# FlightComputer_DeploymentBoard_Rev_B.net
KiCad netlist of a schematic drawn in EAGLE
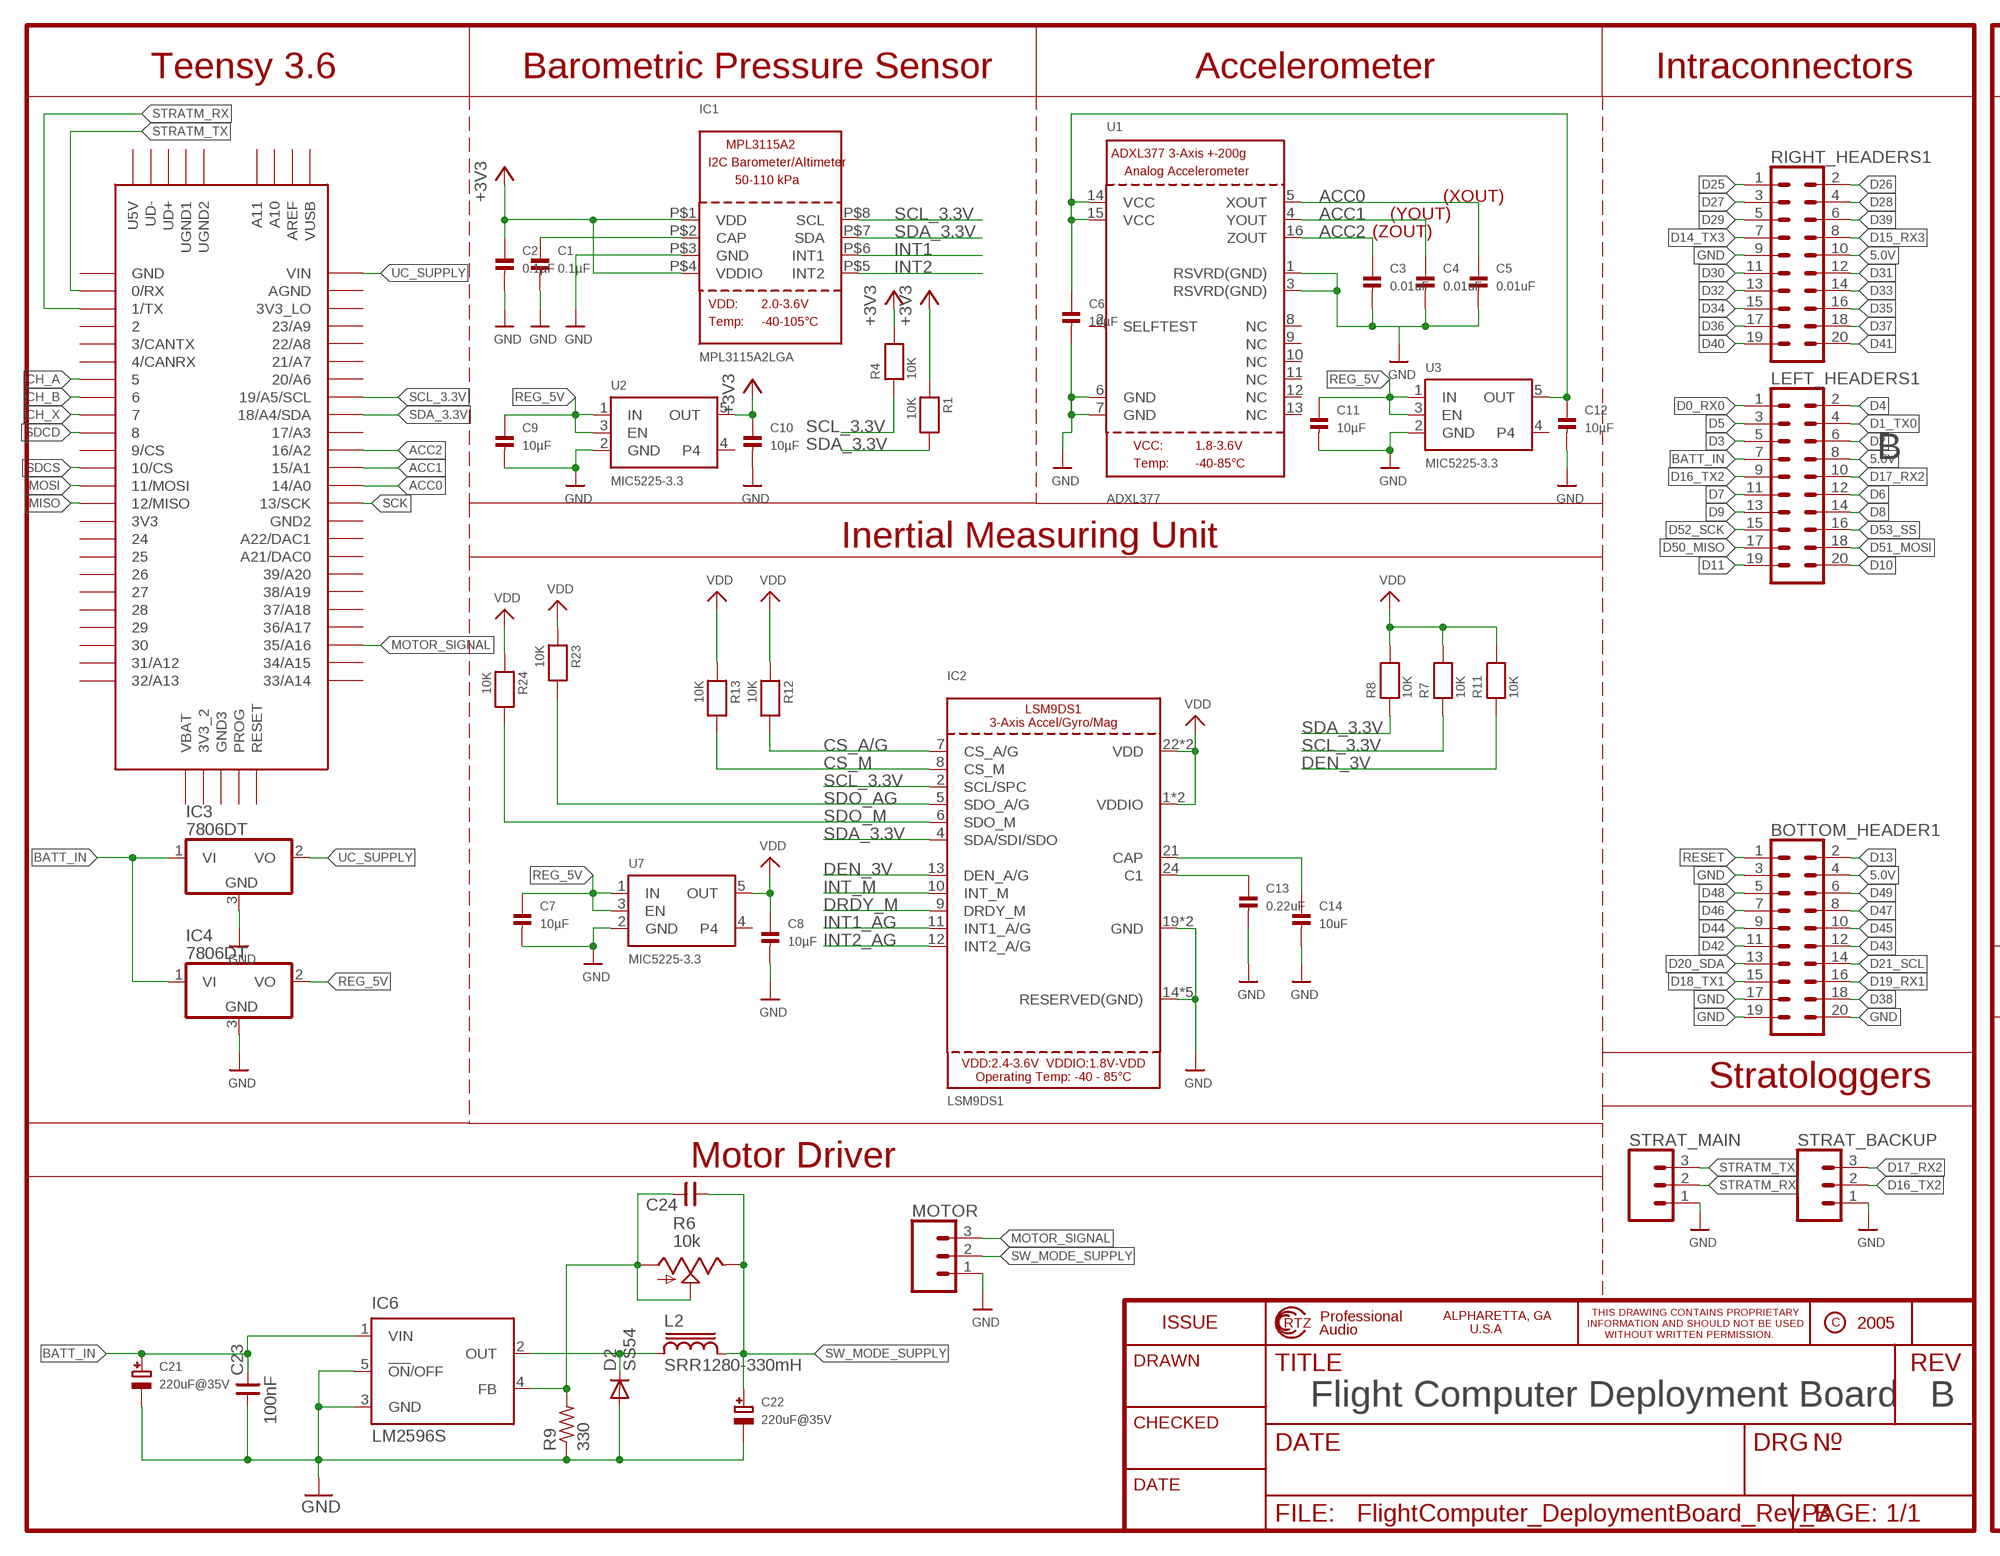
[diagram p0: schematic, sheet 1, part 1 of 2]
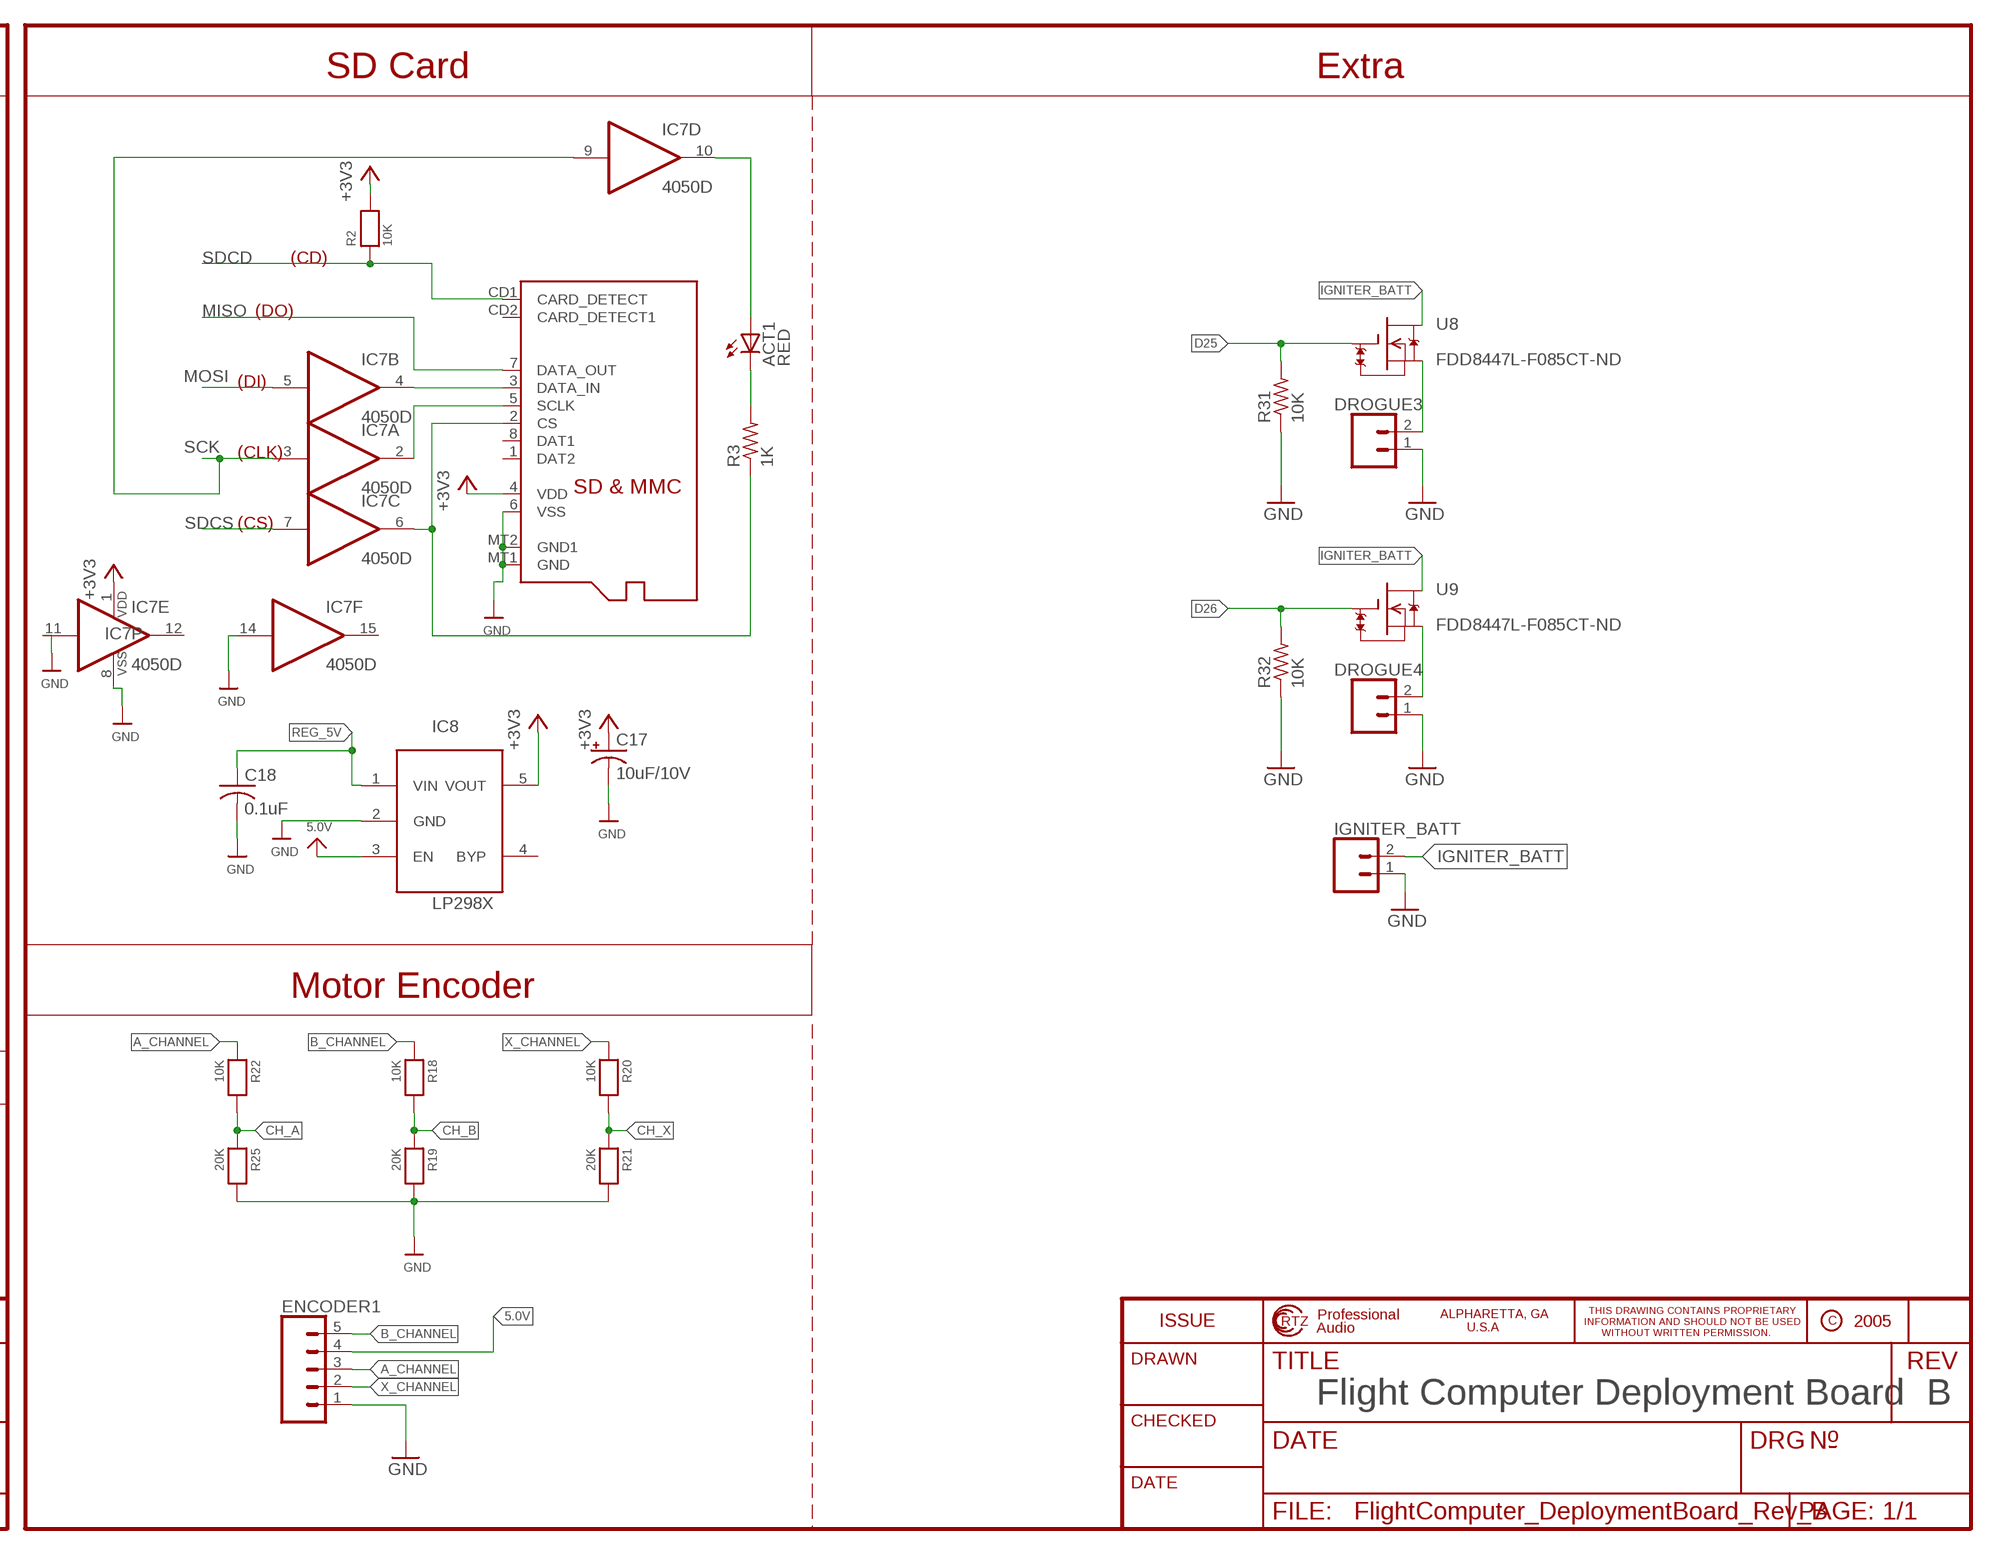
[diagram p1: schematic, sheet 1, part 2 of 2]

(export (version "E")
  (design (tool "Eeschema 10.0.6"))
  (components
    (comp (ref "ACT1")
      (value "RED")
      (footprint "eagle-import:CHIP-LED0805")
      (libsource (lib "eagle-import") (part "LEDCHIP-LED0805"))
    )
    (comp (ref "BOTTOM_HEADER1")
      (value "CONN_10X2")
      (footprint "eagle-import:2X10")
      (libsource (lib "eagle-import") (part "CONN_10X2"))
    )
    (comp (ref "C1")
      (value "0.1µF")
      (footprint "eagle-import:0603")
      (libsource (lib "eagle-import") (part "CAP_CERAMIC0603"))
    )
    (comp (ref "C2")
      (value "0.1µF")
      (footprint "eagle-import:0603")
      (libsource (lib "eagle-import") (part "CAP_CERAMIC0603"))
    )
    (comp (ref "C3")
      (value "0.01uF")
      (footprint "eagle-import:0603")
      (libsource (lib "eagle-import") (part "CAP_CERAMIC0603"))
    )
    (comp (ref "C4")
      (value "0.01uF")
      (footprint "eagle-import:0603")
      (libsource (lib "eagle-import") (part "CAP_CERAMIC0603"))
    )
    (comp (ref "C5")
      (value "0.01uF")
      (footprint "eagle-import:0603")
      (libsource (lib "eagle-import") (part "CAP_CERAMIC0603"))
    )
    (comp (ref "C6")
      (value "10µF")
      (footprint "eagle-import:0603")
      (libsource (lib "eagle-import") (part "CAP_CERAMIC0603"))
    )
    (comp (ref "C7")
      (value "10µF")
      (footprint "eagle-import:0603")
      (libsource (lib "eagle-import") (part "CAP_CERAMIC0603"))
    )
    (comp (ref "C8")
      (value "10µF")
      (footprint "eagle-import:0603")
      (libsource (lib "eagle-import") (part "CAP_CERAMIC0603"))
    )
    (comp (ref "C9")
      (value "10µF")
      (footprint "eagle-import:0603")
      (libsource (lib "eagle-import") (part "CAP_CERAMIC0603"))
    )
    (comp (ref "C10")
      (value "10µF")
      (footprint "eagle-import:0603")
      (libsource (lib "eagle-import") (part "CAP_CERAMIC0603"))
    )
    (comp (ref "C11")
      (value "10µF")
      (footprint "eagle-import:0603")
      (libsource (lib "eagle-import") (part "CAP_CERAMIC0603"))
    )
    (comp (ref "C12")
      (value "10µF")
      (footprint "eagle-import:0603")
      (libsource (lib "eagle-import") (part "CAP_CERAMIC0603"))
    )
    (comp (ref "C13")
      (value "0.22uF")
      (footprint "eagle-import:0603")
      (libsource (lib "eagle-import") (part "CAP_CERAMIC0603"))
    )
    (comp (ref "C14")
      (value "10uF")
      (footprint "eagle-import:0603")
      (libsource (lib "eagle-import") (part "CAP_CERAMIC0603"))
    )
    (comp (ref "C17")
      (value "10uF/10V")
      (footprint "eagle-import:A_3216-18R")
      (libsource (lib "eagle-import") (part "CPOL-USA/3216-18R"))
    )
    (comp (ref "C18")
      (value "0.1uF")
      (footprint "eagle-import:C0805K")
      (libsource (lib "eagle-import") (part "C-USC0805K"))
    )
    (comp (ref "C21")
      (value "220uF@35V")
      (footprint "eagle-import:PANASONIC_D")
      (libsource (lib "eagle-import") (part "CAP_ELECTROLYTICPANASONIC_D"))
    )
    (comp (ref "C22")
      (value "220uF@35V")
      (footprint "eagle-import:PANASONIC_D")
      (libsource (lib "eagle-import") (part "CAP_ELECTROLYTICPANASONIC_D"))
    )
    (comp (ref "C23")
      (value "100nF")
      (footprint "eagle-import:0603")
      (libsource (lib "eagle-import") (part "CNP-0603"))
    )
    (comp (ref "C24")
      (value "CNP-0603")
      (footprint "eagle-import:0603")
      (libsource (lib "eagle-import") (part "CNP-0603"))
    )
    (comp (ref "D2")
      (value "SS54")
      (footprint "eagle-import:DO214AB")
      (fields (field (name "MF") "Fairchild") (field (name "MPN") "S3G"))
      (libsource (lib "eagle-import") (part "S3G"))
    )
    (comp (ref "DROGUE3")
      (value "CONN_023.5MM")
      (footprint "eagle-import:SCREWTERMINAL-3.5MM-2")
      (libsource (lib "eagle-import") (part "CONN_023.5MM"))
    )
    (comp (ref "DROGUE4")
      (value "CONN_023.5MM")
      (footprint "eagle-import:SCREWTERMINAL-3.5MM-2")
      (libsource (lib "eagle-import") (part "CONN_023.5MM"))
    )
    (comp (ref "ENCODER1")
      (value "CONN_05")
      (footprint "eagle-import:1X05")
      (libsource (lib "eagle-import") (part "CONN_05"))
    )
    (comp (ref "IC1")
      (value "MPL3115A2LGA")
      (footprint "eagle-import:LGA8")
      (libsource (lib "eagle-import") (part "MPL3115A2LGA"))
    )
    (comp (ref "IC2")
      (value "LSM9DS1")
      (footprint "eagle-import:LGA24_3.5X3.1MM")
      (libsource (lib "eagle-import") (part "LSM9DS1"))
    )
    (comp (ref "IC3")
      (value "7806DT")
      (footprint "eagle-import:TO252")
      (libsource (lib "eagle-import") (part "78DT06"))
    )
    (comp (ref "IC4")
      (value "7806DT")
      (footprint "eagle-import:TO252")
      (libsource (lib "eagle-import") (part "78DT06"))
    )
    (comp (ref "IC6")
      (value "LM2596S")
      (footprint "eagle-import:TO263-5")
      (fields (field (name "MF") "NATIONAL SEMICONDUCTOR") (field (name "MPN") "LM2596S-ADJ/NOPB"))
      (libsource (lib "eagle-import") (part "LM2596S"))
    )
    (comp (ref "IC7")
      (value "4050D")
      (footprint "eagle-import:SO16")
      (libsource (lib "eagle-import") (part "4050D"))
    )
    (comp (ref "IC8")
      (value "LP298XS")
      (footprint "eagle-import:SOT23-5L")
      (libsource (lib "eagle-import") (part "LP298XS"))
    )
    (comp (ref "IGNITER_BATT")
      (value "CONN_02")
      (footprint "eagle-import:1X02")
      (libsource (lib "eagle-import") (part "CONN_02"))
    )
    (comp (ref "L2")
      (value "SRR1280-330mH")
      (footprint "eagle-import:SRR1280")
      (libsource (lib "eagle-import") (part "SRR1280"))
    )
    (comp (ref "LEFT_HEADERS1")
      (value "CONN_10X2")
      (footprint "eagle-import:2X10")
      (libsource (lib "eagle-import") (part "CONN_10X2"))
    )
    (comp (ref "MOTOR")
      (value "CONN_03")
      (footprint "eagle-import:1X03")
      (libsource (lib "eagle-import") (part "CONN_03"))
    )
    (comp (ref "R1")
      (value "10K")
      (footprint "eagle-import:0603")
      (libsource (lib "eagle-import") (part "RESISTOR0603"))
    )
    (comp (ref "R2")
      (value "10K")
      (footprint "eagle-import:0603")
      (libsource (lib "eagle-import") (part "RESISTOR0603"))
    )
    (comp (ref "R3")
      (value "1K")
      (footprint "eagle-import:R0805")
      (libsource (lib "eagle-import") (part "R-US_R0805"))
    )
    (comp (ref "R4")
      (value "10K")
      (footprint "eagle-import:0603")
      (libsource (lib "eagle-import") (part "RESISTOR0603"))
    )
    (comp (ref "R6")
      (value "10k")
      (footprint "eagle-import:S64W")
      (libsource (lib "eagle-import") (part "TRIM_US-S64W"))
    )
    (comp (ref "R7")
      (value "10K")
      (footprint "eagle-import:0603")
      (libsource (lib "eagle-import") (part "RESISTOR0603"))
    )
    (comp (ref "R8")
      (value "10K")
      (footprint "eagle-import:0603")
      (libsource (lib "eagle-import") (part "RESISTOR0603"))
    )
    (comp (ref "R9")
      (value "330")
      (footprint "eagle-import:R0603")
      (libsource (lib "eagle-import") (part "R-US_R0603"))
    )
    (comp (ref "R11")
      (value "10K")
      (footprint "eagle-import:0603")
      (libsource (lib "eagle-import") (part "RESISTOR0603"))
    )
    (comp (ref "R12")
      (value "10K")
      (footprint "eagle-import:0603")
      (libsource (lib "eagle-import") (part "RESISTOR0603"))
    )
    (comp (ref "R13")
      (value "10K")
      (footprint "eagle-import:0603")
      (libsource (lib "eagle-import") (part "RESISTOR0603"))
    )
    (comp (ref "R18")
      (value "10K")
      (footprint "eagle-import:0603")
      (libsource (lib "eagle-import") (part "RESISTOR0603"))
    )
    (comp (ref "R19")
      (value "20K")
      (footprint "eagle-import:0603")
      (libsource (lib "eagle-import") (part "RESISTOR0603"))
    )
    (comp (ref "R20")
      (value "10K")
      (footprint "eagle-import:0603")
      (libsource (lib "eagle-import") (part "RESISTOR0603"))
    )
    (comp (ref "R21")
      (value "20K")
      (footprint "eagle-import:0603")
      (libsource (lib "eagle-import") (part "RESISTOR0603"))
    )
    (comp (ref "R22")
      (value "10K")
      (footprint "eagle-import:0603")
      (libsource (lib "eagle-import") (part "RESISTOR0603"))
    )
    (comp (ref "R23")
      (value "10K")
      (footprint "eagle-import:0603")
      (libsource (lib "eagle-import") (part "RESISTOR0603"))
    )
    (comp (ref "R24")
      (value "10K")
      (footprint "eagle-import:0603")
      (libsource (lib "eagle-import") (part "RESISTOR0603"))
    )
    (comp (ref "R25")
      (value "20K")
      (footprint "eagle-import:0603")
      (libsource (lib "eagle-import") (part "RESISTOR0603"))
    )
    (comp (ref "R31")
      (value "10K")
      (footprint "eagle-import:R0805")
      (libsource (lib "eagle-import") (part "R-US_R0805"))
    )
    (comp (ref "R32")
      (value "10K")
      (footprint "eagle-import:R0805")
      (libsource (lib "eagle-import") (part "R-US_R0805"))
    )
    (comp (ref "RIGHT_HEADERS1")
      (value "CONN_10X2")
      (footprint "eagle-import:2X10")
      (libsource (lib "eagle-import") (part "CONN_10X2"))
    )
    (comp (ref "STRAT_BACKUP")
      (value "CONN_03")
      (footprint "eagle-import:1X03")
      (libsource (lib "eagle-import") (part "SparkFun-Connectors_513_CONN_03"))
    )
    (comp (ref "STRAT_MAIN")
      (value "CONN_03")
      (footprint "eagle-import:1X03")
      (libsource (lib "eagle-import") (part "SparkFun-Connectors_513_CONN_03"))
    )
    (comp (ref "U$1")
      (value "TEENSY_3.5/3.6")
      (footprint "eagle-import:TEENSY_3.5_3.6")
      (libsource (lib "eagle-import") (part "TEENSY_3.5/3.6"))
    )
    (comp (ref "U$38")
      (value "STRATOLOGGER")
      (footprint "eagle-import:STRATOLOGGER")
      (libsource (lib "eagle-import") (part "STRATOLOGGER"))
    )
    (comp (ref "U1")
      (value "ADXL377")
      (footprint "eagle-import:LFCSP16_LQ")
      (libsource (lib "eagle-import") (part "ACCEL_ADXL377"))
    )
    (comp (ref "U2")
      (value "MIC5225-3.3")
      (footprint "eagle-import:SOT23-5")
      (libsource (lib "eagle-import") (part "VREG_SOT23-5"))
    )
    (comp (ref "U3")
      (value "MIC5225-3.3")
      (footprint "eagle-import:SOT23-5")
      (libsource (lib "eagle-import") (part "VREG_SOT23-5"))
    )
    (comp (ref "U7")
      (value "MIC5225-3.3")
      (footprint "eagle-import:SOT23-5")
      (libsource (lib "eagle-import") (part "VREG_SOT23-5"))
    )
    (comp (ref "U8")
      (value "FDD8447L-F085CT-ND")
      (footprint "eagle-import:TO252")
      (libsource (lib "eagle-import") (part "TSM4ND50"))
    )
    (comp (ref "U9")
      (value "FDD8447L-F085CT-ND")
      (footprint "eagle-import:TO252")
      (libsource (lib "eagle-import") (part "TSM4ND50"))
    )
    (comp (ref "X2")
      (value "MICROSD")
      (footprint "eagle-import:MICROSD")
      (libsource (lib "eagle-import") (part "MICROSD"))
    )
  )
  (nets
    (net (code "1") (name "+3V3") (class "Default")
      (node (ref "C10") (pin "1") (pinfunction "P$1_1") (pintype "passive"))
      (node (ref "C17") (pin "+") (pinfunction "+_+") (pintype "passive"))
      (node (ref "C2") (pin "1") (pinfunction "P$1_1") (pintype "passive"))
      (node (ref "IC1") (pin "P$1") (pinfunction "VDD_P$1") (pintype "power_in"))
      (node (ref "IC1") (pin "P$4") (pinfunction "VDDIO_P$4") (pintype "power_in"))
      (node (ref "IC7") (pin "1") (pinfunction "VDD_1") (pintype "power_in"))
      (node (ref "IC8") (pin "5") (pinfunction "VOUT_5") (pintype "bidirectional"))
      (node (ref "R1") (pin "1") (pinfunction "1_1") (pintype "passive"))
      (node (ref "R2") (pin "2") (pinfunction "2_2") (pintype "passive"))
      (node (ref "R4") (pin "2") (pinfunction "2_2") (pintype "passive"))
      (node (ref "U2") (pin "5") (pinfunction "OUT_5") (pintype "power_in"))
      (node (ref "X2") (pin "4") (pinfunction "VDD_4") (pintype "power_in"))
    )
    (net (code "2") (name "/CS_A{slash}G") (class "Default")
      (node (ref "IC2") (pin "7") (pinfunction "CS_A/G_7") (pintype "bidirectional"))
      (node (ref "R12") (pin "2") (pinfunction "2_2") (pintype "passive"))
    )
    (net (code "3") (name "/CS_M") (class "Default")
      (node (ref "IC2") (pin "8") (pinfunction "CS_M_8") (pintype "bidirectional"))
      (node (ref "R13") (pin "2") (pinfunction "2_2") (pintype "passive"))
    )
    (net (code "4") (name "/DEN_3V") (class "Default")
      (node (ref "IC2") (pin "13") (pinfunction "DEN_A/G_13") (pintype "bidirectional"))
      (node (ref "R11") (pin "1") (pinfunction "1_1") (pintype "passive"))
    )
    (net (code "5") (name "/DRDY_M") (class "Default")
      (node (ref "IC2") (pin "9") (pinfunction "DRDY_M_9") (pintype "bidirectional"))
    )
    (net (code "6") (name "/INT1") (class "Default")
      (node (ref "IC1") (pin "P$6") (pinfunction "INT1_P$6") (pintype "output"))
    )
    (net (code "7") (name "/INT1_AG") (class "Default")
      (node (ref "IC2") (pin "11") (pinfunction "INT1_A/G_11") (pintype "bidirectional"))
    )
    (net (code "8") (name "/INT2") (class "Default")
      (node (ref "IC1") (pin "P$5") (pinfunction "INT2_P$5") (pintype "output"))
    )
    (net (code "9") (name "/INT2_AG") (class "Default")
      (node (ref "IC2") (pin "12") (pinfunction "INT2_A/G_12") (pintype "bidirectional"))
    )
    (net (code "10") (name "/INT_M") (class "Default")
      (node (ref "IC2") (pin "10") (pinfunction "INT_M_10") (pintype "bidirectional"))
    )
    (net (code "11") (name "/SDO_AG") (class "Default")
      (node (ref "IC2") (pin "5") (pinfunction "SDO_A/G_5") (pintype "bidirectional"))
      (node (ref "R23") (pin "2") (pinfunction "2_2") (pintype "passive"))
    )
    (net (code "12") (name "/SDO_M") (class "Default")
      (node (ref "IC2") (pin "6") (pinfunction "SDO_M_6") (pintype "bidirectional"))
      (node (ref "R24") (pin "2") (pinfunction "2_2") (pintype "passive"))
    )
    (net (code "13") (name "5.0V") (class "Default")
      (node (ref "BOTTOM_HEADER1") (pin "4") (pinfunction "4_4") (pintype "passive"))
      (node (ref "ENCODER1") (pin "4") (pinfunction "4_4") (pintype "passive"))
      (node (ref "IC8") (pin "3") (pinfunction "EN_3") (pintype "bidirectional"))
      (node (ref "LEFT_HEADERS1") (pin "8") (pinfunction "8_8") (pintype "passive"))
      (node (ref "RIGHT_HEADERS1") (pin "10") (pinfunction "10_10") (pintype "passive"))
    )
    (net (code "14") (name "ACC0") (class "Default")
      (node (ref "C5") (pin "1") (pinfunction "P$1_1") (pintype "passive"))
      (node (ref "U$1") (pin "14/A0") (pinfunction "14/A0_14/A0") (pintype "bidirectional"))
      (node (ref "U1") (pin "5") (pinfunction "XOUT_5") (pintype "output"))
    )
    (net (code "15") (name "ACC1") (class "Default")
      (node (ref "C4") (pin "1") (pinfunction "P$1_1") (pintype "passive"))
      (node (ref "U$1") (pin "15/A1") (pinfunction "15/A1_15/A1") (pintype "bidirectional"))
      (node (ref "U1") (pin "4") (pinfunction "YOUT_4") (pintype "output"))
    )
    (net (code "16") (name "ACC2") (class "Default")
      (node (ref "C3") (pin "1") (pinfunction "P$1_1") (pintype "passive"))
      (node (ref "U$1") (pin "16/A2") (pinfunction "16/A2_16/A2") (pintype "bidirectional"))
      (node (ref "U1") (pin "16") (pinfunction "ZOUT_16") (pintype "output"))
    )
    (net (code "17") (name "A_CHANNEL") (class "Default")
      (node (ref "ENCODER1") (pin "3") (pinfunction "3_3") (pintype "passive"))
      (node (ref "R22") (pin "1") (pinfunction "1_1") (pintype "passive"))
    )
    (net (code "18") (name "BATT_IN") (class "Default")
      (node (ref "C21") (pin "+") (pinfunction "+_+") (pintype "passive"))
      (node (ref "C23") (pin "2") (pinfunction "2_2") (pintype "passive"))
      (node (ref "IC3") (pin "1") (pinfunction "VI_1") (pintype "input"))
      (node (ref "IC4") (pin "1") (pinfunction "VI_1") (pintype "input"))
      (node (ref "IC6") (pin "1") (pinfunction "VIN_1") (pintype "input"))
      (node (ref "LEFT_HEADERS1") (pin "7") (pinfunction "7_7") (pintype "passive"))
    )
    (net (code "19") (name "B_CHANNEL") (class "Default")
      (node (ref "ENCODER1") (pin "5") (pinfunction "5_5") (pintype "passive"))
      (node (ref "R18") (pin "1") (pinfunction "1_1") (pintype "passive"))
    )
    (net (code "20") (name "CH_A") (class "Default")
      (node (ref "R22") (pin "2") (pinfunction "2_2") (pintype "passive"))
      (node (ref "R25") (pin "1") (pinfunction "1_1") (pintype "passive"))
      (node (ref "U$1") (pin "5") (pinfunction "5_5") (pintype "bidirectional"))
    )
    (net (code "21") (name "CH_B") (class "Default")
      (node (ref "R18") (pin "2") (pinfunction "2_2") (pintype "passive"))
      (node (ref "R19") (pin "1") (pinfunction "1_1") (pintype "passive"))
      (node (ref "U$1") (pin "6") (pinfunction "6_6") (pintype "bidirectional"))
    )
    (net (code "22") (name "CH_X") (class "Default")
      (node (ref "R20") (pin "2") (pinfunction "2_2") (pintype "passive"))
      (node (ref "R21") (pin "1") (pinfunction "1_1") (pintype "passive"))
      (node (ref "U$1") (pin "7") (pinfunction "7_7") (pintype "bidirectional"))
    )
    (net (code "23") (name "D0_RX0") (class "Default")
      (node (ref "LEFT_HEADERS1") (pin "1") (pinfunction "1_1") (pintype "passive"))
    )
    (net (code "24") (name "D1_TX0") (class "Default")
      (node (ref "LEFT_HEADERS1") (pin "4") (pinfunction "4_4") (pintype "passive"))
    )
    (net (code "25") (name "D2") (class "Default")
      (node (ref "LEFT_HEADERS1") (pin "6") (pinfunction "6_6") (pintype "passive"))
    )
    (net (code "26") (name "D3") (class "Default")
      (node (ref "LEFT_HEADERS1") (pin "5") (pinfunction "5_5") (pintype "passive"))
    )
    (net (code "27") (name "D4") (class "Default")
      (node (ref "LEFT_HEADERS1") (pin "2") (pinfunction "2_2") (pintype "passive"))
    )
    (net (code "28") (name "D5") (class "Default")
      (node (ref "LEFT_HEADERS1") (pin "3") (pinfunction "3_3") (pintype "passive"))
    )
    (net (code "29") (name "D6") (class "Default")
      (node (ref "LEFT_HEADERS1") (pin "12") (pinfunction "12_12") (pintype "passive"))
    )
    (net (code "30") (name "D7") (class "Default")
      (node (ref "LEFT_HEADERS1") (pin "11") (pinfunction "11_11") (pintype "passive"))
    )
    (net (code "31") (name "D8") (class "Default")
      (node (ref "LEFT_HEADERS1") (pin "14") (pinfunction "14_14") (pintype "passive"))
    )
    (net (code "32") (name "D9") (class "Default")
      (node (ref "LEFT_HEADERS1") (pin "13") (pinfunction "13_13") (pintype "passive"))
    )
    (net (code "33") (name "D10") (class "Default")
      (node (ref "LEFT_HEADERS1") (pin "20") (pinfunction "20_20") (pintype "passive"))
    )
    (net (code "34") (name "D11") (class "Default")
      (node (ref "LEFT_HEADERS1") (pin "19") (pinfunction "19_19") (pintype "passive"))
    )
    (net (code "35") (name "D13") (class "Default")
      (node (ref "BOTTOM_HEADER1") (pin "2") (pinfunction "2_2") (pintype "passive"))
    )
    (net (code "36") (name "D14_TX3") (class "Default")
      (node (ref "RIGHT_HEADERS1") (pin "7") (pinfunction "7_7") (pintype "passive"))
    )
    (net (code "37") (name "D15_RX3") (class "Default")
      (node (ref "RIGHT_HEADERS1") (pin "8") (pinfunction "8_8") (pintype "passive"))
    )
    (net (code "38") (name "D16_TX2") (class "Default")
      (node (ref "LEFT_HEADERS1") (pin "9") (pinfunction "9_9") (pintype "passive"))
      (node (ref "STRAT_BACKUP") (pin "2") (pinfunction "2_2") (pintype "passive"))
    )
    (net (code "39") (name "D17_RX2") (class "Default")
      (node (ref "LEFT_HEADERS1") (pin "10") (pinfunction "10_10") (pintype "passive"))
      (node (ref "STRAT_BACKUP") (pin "3") (pinfunction "3_3") (pintype "passive"))
    )
    (net (code "40") (name "D18_TX1") (class "Default")
      (node (ref "BOTTOM_HEADER1") (pin "15") (pinfunction "15_15") (pintype "passive"))
    )
    (net (code "41") (name "D19_RX1") (class "Default")
      (node (ref "BOTTOM_HEADER1") (pin "16") (pinfunction "16_16") (pintype "passive"))
    )
    (net (code "42") (name "D20_SDA") (class "Default")
      (node (ref "BOTTOM_HEADER1") (pin "13") (pinfunction "13_13") (pintype "passive"))
    )
    (net (code "43") (name "D21_SCL") (class "Default")
      (node (ref "BOTTOM_HEADER1") (pin "14") (pinfunction "14_14") (pintype "passive"))
    )
    (net (code "44") (name "D25") (class "Default")
      (node (ref "R31") (pin "2") (pinfunction "2_2") (pintype "passive"))
      (node (ref "RIGHT_HEADERS1") (pin "1") (pinfunction "1_1") (pintype "passive"))
      (node (ref "U8") (pin "G") (pinfunction "G_G") (pintype "passive"))
    )
    (net (code "45") (name "D26") (class "Default")
      (node (ref "R32") (pin "2") (pinfunction "2_2") (pintype "passive"))
      (node (ref "RIGHT_HEADERS1") (pin "2") (pinfunction "2_2") (pintype "passive"))
      (node (ref "U9") (pin "G") (pinfunction "G_G") (pintype "passive"))
    )
    (net (code "46") (name "D27") (class "Default")
      (node (ref "RIGHT_HEADERS1") (pin "3") (pinfunction "3_3") (pintype "passive"))
    )
    (net (code "47") (name "D28") (class "Default")
      (node (ref "RIGHT_HEADERS1") (pin "4") (pinfunction "4_4") (pintype "passive"))
    )
    (net (code "48") (name "D29") (class "Default")
      (node (ref "RIGHT_HEADERS1") (pin "5") (pinfunction "5_5") (pintype "passive"))
    )
    (net (code "49") (name "D30") (class "Default")
      (node (ref "RIGHT_HEADERS1") (pin "11") (pinfunction "11_11") (pintype "passive"))
    )
    (net (code "50") (name "D31") (class "Default")
      (node (ref "RIGHT_HEADERS1") (pin "12") (pinfunction "12_12") (pintype "passive"))
    )
    (net (code "51") (name "D32") (class "Default")
      (node (ref "RIGHT_HEADERS1") (pin "13") (pinfunction "13_13") (pintype "passive"))
    )
    (net (code "52") (name "D33") (class "Default")
      (node (ref "RIGHT_HEADERS1") (pin "14") (pinfunction "14_14") (pintype "passive"))
    )
    (net (code "53") (name "D34") (class "Default")
      (node (ref "RIGHT_HEADERS1") (pin "15") (pinfunction "15_15") (pintype "passive"))
    )
    (net (code "54") (name "D35") (class "Default")
      (node (ref "RIGHT_HEADERS1") (pin "16") (pinfunction "16_16") (pintype "passive"))
    )
    (net (code "55") (name "D36") (class "Default")
      (node (ref "RIGHT_HEADERS1") (pin "17") (pinfunction "17_17") (pintype "passive"))
    )
    (net (code "56") (name "D37") (class "Default")
      (node (ref "RIGHT_HEADERS1") (pin "18") (pinfunction "18_18") (pintype "passive"))
    )
    (net (code "57") (name "D38") (class "Default")
      (node (ref "BOTTOM_HEADER1") (pin "18") (pinfunction "18_18") (pintype "passive"))
    )
    (net (code "58") (name "D39") (class "Default")
      (node (ref "RIGHT_HEADERS1") (pin "6") (pinfunction "6_6") (pintype "passive"))
    )
    (net (code "59") (name "D40") (class "Default")
      (node (ref "RIGHT_HEADERS1") (pin "19") (pinfunction "19_19") (pintype "passive"))
    )
    (net (code "60") (name "D41") (class "Default")
      (node (ref "RIGHT_HEADERS1") (pin "20") (pinfunction "20_20") (pintype "passive"))
    )
    (net (code "61") (name "D42") (class "Default")
      (node (ref "BOTTOM_HEADER1") (pin "11") (pinfunction "11_11") (pintype "passive"))
    )
    (net (code "62") (name "D43") (class "Default")
      (node (ref "BOTTOM_HEADER1") (pin "12") (pinfunction "12_12") (pintype "passive"))
    )
    (net (code "63") (name "D44") (class "Default")
      (node (ref "BOTTOM_HEADER1") (pin "9") (pinfunction "9_9") (pintype "passive"))
    )
    (net (code "64") (name "D45") (class "Default")
      (node (ref "BOTTOM_HEADER1") (pin "10") (pinfunction "10_10") (pintype "passive"))
    )
    (net (code "65") (name "D46") (class "Default")
      (node (ref "BOTTOM_HEADER1") (pin "7") (pinfunction "7_7") (pintype "passive"))
    )
    (net (code "66") (name "D47") (class "Default")
      (node (ref "BOTTOM_HEADER1") (pin "8") (pinfunction "8_8") (pintype "passive"))
    )
    (net (code "67") (name "D48") (class "Default")
      (node (ref "BOTTOM_HEADER1") (pin "5") (pinfunction "5_5") (pintype "passive"))
    )
    (net (code "68") (name "D49") (class "Default")
      (node (ref "BOTTOM_HEADER1") (pin "6") (pinfunction "6_6") (pintype "passive"))
    )
    (net (code "69") (name "D50_MISO") (class "Default")
      (node (ref "LEFT_HEADERS1") (pin "17") (pinfunction "17_17") (pintype "passive"))
    )
    (net (code "70") (name "D51_MOSI") (class "Default")
      (node (ref "LEFT_HEADERS1") (pin "18") (pinfunction "18_18") (pintype "passive"))
    )
    (net (code "71") (name "D52_SCK") (class "Default")
      (node (ref "LEFT_HEADERS1") (pin "15") (pinfunction "15_15") (pintype "passive"))
    )
    (net (code "72") (name "D53_SS") (class "Default")
      (node (ref "LEFT_HEADERS1") (pin "16") (pinfunction "16_16") (pintype "passive"))
    )
    (net (code "73") (name "GND") (class "Default")
      (node (ref "BOTTOM_HEADER1") (pin "17") (pinfunction "17_17") (pintype "passive"))
      (node (ref "BOTTOM_HEADER1") (pin "19") (pinfunction "19_19") (pintype "passive"))
      (node (ref "BOTTOM_HEADER1") (pin "20") (pinfunction "20_20") (pintype "passive"))
      (node (ref "BOTTOM_HEADER1") (pin "3") (pinfunction "3_3") (pintype "passive"))
      (node (ref "C1") (pin "2") (pinfunction "P$2_2") (pintype "passive"))
      (node (ref "C10") (pin "2") (pinfunction "P$2_2") (pintype "passive"))
      (node (ref "C11") (pin "2") (pinfunction "P$2_2") (pintype "passive"))
      (node (ref "C12") (pin "2") (pinfunction "P$2_2") (pintype "passive"))
      (node (ref "C13") (pin "2") (pinfunction "P$2_2") (pintype "passive"))
      (node (ref "C14") (pin "2") (pinfunction "P$2_2") (pintype "passive"))
      (node (ref "C17") (pin "-") (pinfunction "-_-") (pintype "passive"))
      (node (ref "C18") (pin "2") (pinfunction "2_2") (pintype "passive"))
      (node (ref "C2") (pin "2") (pinfunction "P$2_2") (pintype "passive"))
      (node (ref "C21") (pin "-") (pinfunction "-_-") (pintype "passive"))
      (node (ref "C22") (pin "-") (pinfunction "-_-") (pintype "passive"))
      (node (ref "C23") (pin "1") (pinfunction "1_1") (pintype "passive"))
      (node (ref "C3") (pin "2") (pinfunction "P$2_2") (pintype "passive"))
      (node (ref "C4") (pin "2") (pinfunction "P$2_2") (pintype "passive"))
      (node (ref "C5") (pin "2") (pinfunction "P$2_2") (pintype "passive"))
      (node (ref "C6") (pin "2") (pinfunction "P$2_2") (pintype "passive"))
      (node (ref "C7") (pin "2") (pinfunction "P$2_2") (pintype "passive"))
      (node (ref "C8") (pin "2") (pinfunction "P$2_2") (pintype "passive"))
      (node (ref "C9") (pin "2") (pinfunction "P$2_2") (pintype "passive"))
      (node (ref "D2") (pin "A") (pinfunction "A_A") (pintype "passive"))
      (node (ref "DROGUE3") (pin "1") (pinfunction "1_1") (pintype "passive"))
      (node (ref "DROGUE4") (pin "1") (pinfunction "1_1") (pintype "passive"))
      (node (ref "ENCODER1") (pin "1") (pinfunction "1_1") (pintype "passive"))
      (node (ref "IC1") (pin "P$3") (pinfunction "GND_P$3") (pintype "power_in"))
      (node (ref "IC2") (pin "14") (pinfunction "RESERVED(GND)_14") (pintype "power_in"))
      (node (ref "IC2") (pin "15") (pinfunction "RESERVED(GND)_15") (pintype "power_in"))
      (node (ref "IC2") (pin "16") (pinfunction "RESERVED(GND)_16") (pintype "power_in"))
      (node (ref "IC2") (pin "17") (pinfunction "RESERVED(GND)_17") (pintype "power_in"))
      (node (ref "IC2") (pin "18") (pinfunction "RESERVED(GND)_18") (pintype "power_in"))
      (node (ref "IC2") (pin "19") (pinfunction "GND_19") (pintype "power_in"))
      (node (ref "IC2") (pin "20") (pinfunction "GND_20") (pintype "power_in"))
      (node (ref "IC3") (pin "3") (pinfunction "GND_3") (pintype "passive"))
      (node (ref "IC4") (pin "3") (pinfunction "GND_3") (pintype "passive"))
      (node (ref "IC6") (pin "3") (pinfunction "GND_3") (pintype "power_in"))
      (node (ref "IC6") (pin "5") (pinfunction "~{ON}/OFF_5") (pintype "input"))
      (node (ref "IC7") (pin "11") (pinfunction "I_11") (pintype "input"))
      (node (ref "IC7") (pin "14") (pinfunction "I_14") (pintype "input"))
      (node (ref "IC7") (pin "8") (pinfunction "VSS_8") (pintype "power_in"))
      (node (ref "IC8") (pin "2") (pinfunction "GND_2") (pintype "bidirectional"))
      (node (ref "IGNITER_BATT") (pin "1") (pinfunction "1_1") (pintype "passive"))
      (node (ref "MOTOR") (pin "1") (pinfunction "1_1") (pintype "passive"))
      (node (ref "R19") (pin "2") (pinfunction "2_2") (pintype "passive"))
      (node (ref "R21") (pin "2") (pinfunction "2_2") (pintype "passive"))
      (node (ref "R25") (pin "2") (pinfunction "2_2") (pintype "passive"))
      (node (ref "R31") (pin "1") (pinfunction "1_1") (pintype "passive"))
      (node (ref "R32") (pin "1") (pinfunction "1_1") (pintype "passive"))
      (node (ref "R9") (pin "1") (pinfunction "1_1") (pintype "passive"))
      (node (ref "RIGHT_HEADERS1") (pin "9") (pinfunction "9_9") (pintype "passive"))
      (node (ref "STRAT_BACKUP") (pin "1") (pinfunction "1_1") (pintype "passive"))
      (node (ref "STRAT_MAIN") (pin "1") (pinfunction "1_1") (pintype "passive"))
      (node (ref "U1") (pin "1") (pinfunction "RSVRD(GND)_1") (pintype "bidirectional"))
      (node (ref "U1") (pin "3") (pinfunction "RSVRD(GND)_3") (pintype "bidirectional"))
      (node (ref "U1") (pin "6") (pinfunction "GND_6") (pintype "power_in"))
      (node (ref "U1") (pin "7") (pinfunction "GND_7") (pintype "power_in"))
      (node (ref "U2") (pin "2") (pinfunction "GND_2") (pintype "power_in"))
      (node (ref "U3") (pin "2") (pinfunction "GND_2") (pintype "power_in"))
      (node (ref "U7") (pin "2") (pinfunction "GND_2") (pintype "power_in"))
      (node (ref "X2") (pin "6") (pinfunction "VSS_6") (pintype "power_in"))
      (node (ref "X2") (pin "MT1") (pinfunction "GND_MT1") (pintype "power_in"))
      (node (ref "X2") (pin "MT2") (pinfunction "GND1_MT2") (pintype "power_in"))
    )
    (net (code "74") (name "IGNITER_BATT") (class "Default")
      (node (ref "IGNITER_BATT") (pin "2") (pinfunction "2_2") (pintype "passive"))
      (node (ref "U8") (pin "D") (pinfunction "D_D") (pintype "passive"))
      (node (ref "U9") (pin "D") (pinfunction "D_D") (pintype "passive"))
    )
    (net (code "75") (name "MISO") (class "Default")
      (node (ref "U$1") (pin "12/MISO") (pinfunction "12/MISO_12/MISO") (pintype "bidirectional"))
      (node (ref "X2") (pin "7") (pinfunction "DATA_OUT_7") (pintype "output"))
    )
    (net (code "76") (name "MOSI") (class "Default")
      (node (ref "IC7") (pin "5") (pinfunction "I_5") (pintype "input"))
      (node (ref "U$1") (pin "11/MOSI") (pinfunction "11/MOSI_11/MOSI") (pintype "bidirectional"))
    )
    (net (code "77") (name "MOTOR_SIGNAL") (class "Default")
      (node (ref "MOTOR") (pin "3") (pinfunction "3_3") (pintype "passive"))
      (node (ref "U$1") (pin "35/A16") (pinfunction "35/A16_35/A16") (pintype "bidirectional"))
    )
    (net (code "78") (name "Net-(ACT1-PadC)") (class "Default")
      (node (ref "ACT1") (pin "C") (pinfunction "C_C") (pintype "passive"))
      (node (ref "R3") (pin "2") (pinfunction "2_2") (pintype "passive"))
    )
    (net (code "79") (name "Net-(C1-P$1)") (class "Default")
      (node (ref "C1") (pin "1") (pinfunction "P$1_1") (pintype "passive"))
      (node (ref "IC1") (pin "P$2") (pinfunction "CAP_P$2") (pintype "passive"))
    )
    (net (code "80") (name "Net-(C12-P$1)") (class "Default")
      (node (ref "C12") (pin "1") (pinfunction "P$1_1") (pintype "passive"))
      (node (ref "C6") (pin "1") (pinfunction "P$1_1") (pintype "passive"))
      (node (ref "U1") (pin "14") (pinfunction "VCC_14") (pintype "power_in"))
      (node (ref "U1") (pin "15") (pinfunction "VCC_15") (pintype "power_in"))
      (node (ref "U3") (pin "5") (pinfunction "OUT_5") (pintype "power_in"))
    )
    (net (code "81") (name "Net-(C13-P$1)") (class "Default")
      (node (ref "C13") (pin "1") (pinfunction "P$1_1") (pintype "passive"))
      (node (ref "IC2") (pin "24") (pinfunction "C1_24") (pintype "bidirectional"))
    )
    (net (code "82") (name "Net-(C14-P$1)") (class "Default")
      (node (ref "C14") (pin "1") (pinfunction "P$1_1") (pintype "passive"))
      (node (ref "IC2") (pin "21") (pinfunction "CAP_21") (pintype "bidirectional"))
    )
    (net (code "83") (name "Net-(DROGUE3-Pad2)") (class "Default")
      (node (ref "DROGUE3") (pin "2") (pinfunction "2_2") (pintype "passive"))
      (node (ref "U8") (pin "S") (pinfunction "S_S") (pintype "passive"))
    )
    (net (code "84") (name "Net-(DROGUE4-Pad2)") (class "Default")
      (node (ref "DROGUE4") (pin "2") (pinfunction "2_2") (pintype "passive"))
      (node (ref "U9") (pin "S") (pinfunction "S_S") (pintype "passive"))
    )
    (net (code "85") (name "Net-(IC6-FB)") (class "Default")
      (node (ref "C24") (pin "2") (pinfunction "2_2") (pintype "passive"))
      (node (ref "IC6") (pin "4") (pinfunction "FB_4") (pintype "input"))
      (node (ref "R6") (pin "A") (pinfunction "A_A") (pintype "passive"))
      (node (ref "R6") (pin "S") (pinfunction "S_S") (pintype "passive"))
      (node (ref "R9") (pin "2") (pinfunction "2_2") (pintype "passive"))
    )
    (net (code "86") (name "Net-(IC6-OUT)") (class "Default")
      (node (ref "D2") (pin "C") (pinfunction "C_C") (pintype "passive"))
      (node (ref "IC6") (pin "2") (pinfunction "OUT_2") (pintype "output"))
      (node (ref "L2") (pin "1") (pinfunction "1_1") (pintype "passive"))
    )
    (net (code "87") (name "Net-(IC7A-O)") (class "Default")
      (node (ref "IC7") (pin "2") (pinfunction "O_2") (pintype "output"))
      (node (ref "X2") (pin "5") (pinfunction "SCLK_5") (pintype "input"))
    )
    (net (code "88") (name "Net-(IC7B-O)") (class "Default")
      (node (ref "IC7") (pin "4") (pinfunction "O_4") (pintype "output"))
      (node (ref "X2") (pin "3") (pinfunction "DATA_IN_3") (pintype "input"))
    )
    (net (code "89") (name "Net-(IC7C-O)") (class "Default")
      (node (ref "IC7") (pin "6") (pinfunction "O_6") (pintype "output"))
      (node (ref "R3") (pin "1") (pinfunction "1_1") (pintype "passive"))
      (node (ref "X2") (pin "2") (pinfunction "CS_2") (pintype "input"))
    )
    (net (code "90") (name "Net-(IC7D-O)") (class "Default")
      (node (ref "ACT1") (pin "A") (pinfunction "A_A") (pintype "passive"))
      (node (ref "IC7") (pin "10") (pinfunction "O_10") (pintype "output"))
    )
    (net (code "91") (name "REG_5V") (class "Default")
      (node (ref "C11") (pin "1") (pinfunction "P$1_1") (pintype "passive"))
      (node (ref "C18") (pin "1") (pinfunction "1_1") (pintype "passive"))
      (node (ref "C7") (pin "1") (pinfunction "P$1_1") (pintype "passive"))
      (node (ref "C9") (pin "1") (pinfunction "P$1_1") (pintype "passive"))
      (node (ref "IC4") (pin "2") (pinfunction "VO_2") (pintype "passive"))
      (node (ref "IC8") (pin "1") (pinfunction "VIN_1") (pintype "bidirectional"))
      (node (ref "U2") (pin "1") (pinfunction "IN_1") (pintype "power_in"))
      (node (ref "U2") (pin "3") (pinfunction "EN_3") (pintype "input"))
      (node (ref "U3") (pin "1") (pinfunction "IN_1") (pintype "power_in"))
      (node (ref "U3") (pin "3") (pinfunction "EN_3") (pintype "input"))
      (node (ref "U7") (pin "1") (pinfunction "IN_1") (pintype "power_in"))
      (node (ref "U7") (pin "3") (pinfunction "EN_3") (pintype "input"))
    )
    (net (code "92") (name "RESET") (class "Default")
      (node (ref "BOTTOM_HEADER1") (pin "1") (pinfunction "1_1") (pintype "passive"))
    )
    (net (code "93") (name "SCK") (class "Default")
      (node (ref "IC7") (pin "3") (pinfunction "I_3") (pintype "input"))
      (node (ref "IC7") (pin "9") (pinfunction "I_9") (pintype "input"))
      (node (ref "U$1") (pin "13/SCK") (pinfunction "13/SCK_13/SCK") (pintype "bidirectional"))
    )
    (net (code "94") (name "SCL_3.3V") (class "Default")
      (node (ref "IC1") (pin "P$8") (pinfunction "SCL_P$8") (pintype "bidirectional"))
      (node (ref "IC2") (pin "2") (pinfunction "SCL/SPC_2") (pintype "bidirectional"))
      (node (ref "R4") (pin "1") (pinfunction "1_1") (pintype "passive"))
      (node (ref "R7") (pin "1") (pinfunction "1_1") (pintype "passive"))
      (node (ref "U$1") (pin "19/A5/SCL") (pinfunction "19/A5/SCL_19/A5/SCL") (pintype "bidirectional"))
    )
    (net (code "95") (name "SDA_3.3V") (class "Default")
      (node (ref "IC1") (pin "P$7") (pinfunction "SDA_P$7") (pintype "bidirectional"))
      (node (ref "IC2") (pin "4") (pinfunction "SDA/SDI/SDO_4") (pintype "bidirectional"))
      (node (ref "R1") (pin "2") (pinfunction "2_2") (pintype "passive"))
      (node (ref "R8") (pin "1") (pinfunction "1_1") (pintype "passive"))
      (node (ref "U$1") (pin "18/A4/SDA") (pinfunction "18/A4/SDA_18/A4/SDA") (pintype "bidirectional"))
    )
    (net (code "96") (name "SDCD") (class "Default")
      (node (ref "R2") (pin "1") (pinfunction "1_1") (pintype "passive"))
      (node (ref "U$1") (pin "8") (pinfunction "8_8") (pintype "bidirectional"))
      (node (ref "X2") (pin "CD1") (pinfunction "CARD_DETECT_CD1") (pintype "passive"))
    )
    (net (code "97") (name "SDCS") (class "Default")
      (node (ref "IC7") (pin "7") (pinfunction "I_7") (pintype "input"))
      (node (ref "U$1") (pin "10/CS") (pinfunction "10/CS_10/CS") (pintype "bidirectional"))
    )
    (net (code "98") (name "STRATM_RX") (class "Default")
      (node (ref "STRAT_MAIN") (pin "2") (pinfunction "2_2") (pintype "passive"))
      (node (ref "U$1") (pin "1/TX") (pinfunction "1/TX_1/TX") (pintype "bidirectional"))
    )
    (net (code "99") (name "STRATM_TX") (class "Default")
      (node (ref "STRAT_MAIN") (pin "3") (pinfunction "3_3") (pintype "passive"))
      (node (ref "U$1") (pin "0/RX") (pinfunction "0/RX_0/RX") (pintype "bidirectional"))
    )
    (net (code "100") (name "SW_MODE_SUPPLY") (class "Default")
      (node (ref "C22") (pin "+") (pinfunction "+_+") (pintype "passive"))
      (node (ref "C24") (pin "1") (pinfunction "1_1") (pintype "passive"))
      (node (ref "L2") (pin "2") (pinfunction "2_2") (pintype "passive"))
      (node (ref "MOTOR") (pin "2") (pinfunction "2_2") (pintype "passive"))
      (node (ref "R6") (pin "E") (pinfunction "E_E") (pintype "passive"))
    )
    (net (code "101") (name "UC_SUPPLY") (class "Default")
      (node (ref "IC3") (pin "2") (pinfunction "VO_2") (pintype "passive"))
      (node (ref "U$1") (pin "VIN") (pinfunction "VIN_VIN") (pintype "bidirectional"))
    )
    (net (code "102") (name "VDD") (class "Default")
      (node (ref "C8") (pin "1") (pinfunction "P$1_1") (pintype "passive"))
      (node (ref "IC2") (pin "1") (pinfunction "VDDIO_1") (pintype "power_in"))
      (node (ref "IC2") (pin "22") (pinfunction "VDD_22") (pintype "power_in"))
      (node (ref "IC2") (pin "23") (pinfunction "VDD_23") (pintype "power_in"))
      (node (ref "IC2") (pin "3") (pinfunction "VDDIO_3") (pintype "power_in"))
      (node (ref "R11") (pin "2") (pinfunction "2_2") (pintype "passive"))
      (node (ref "R12") (pin "1") (pinfunction "1_1") (pintype "passive"))
      (node (ref "R13") (pin "1") (pinfunction "1_1") (pintype "passive"))
      (node (ref "R23") (pin "1") (pinfunction "1_1") (pintype "passive"))
      (node (ref "R24") (pin "1") (pinfunction "1_1") (pintype "passive"))
      (node (ref "R7") (pin "2") (pinfunction "2_2") (pintype "passive"))
      (node (ref "R8") (pin "2") (pinfunction "2_2") (pintype "passive"))
      (node (ref "U7") (pin "5") (pinfunction "OUT_5") (pintype "power_in"))
    )
    (net (code "103") (name "X_CHANNEL") (class "Default")
      (node (ref "ENCODER1") (pin "2") (pinfunction "2_2") (pintype "passive"))
      (node (ref "R20") (pin "1") (pinfunction "1_1") (pintype "passive"))
    )
    (net (code "104") (name "unconnected-(IC7E-O-Pad12)") (class "Default")
      (node (ref "IC7") (pin "12") (pinfunction "O_12") (pintype "output"))
    )
    (net (code "105") (name "unconnected-(IC7F-O-Pad15)") (class "Default")
      (node (ref "IC7") (pin "15") (pinfunction "O_15") (pintype "output"))
    )
    (net (code "106") (name "unconnected-(IC8-BYP-Pad4)") (class "Default")
      (node (ref "IC8") (pin "4") (pinfunction "BYP_4") (pintype "bidirectional"))
    )
    (net (code "107") (name "unconnected-(U$1-A21{slash}DAC0-Pad21{slash}DAC0)") (class "Default")
      (node (ref "U$1") (pin "21/DAC0") (pinfunction "A21/DAC0_21/DAC0") (pintype "bidirectional"))
    )
    (net (code "108") (name "unconnected-(U$1-Pad2)") (class "Default")
      (node (ref "U$1") (pin "2") (pinfunction "2_2") (pintype "bidirectional"))
    )
    (net (code "109") (name "unconnected-(U$1-Pad3V3)") (class "Default")
      (node (ref "U$1") (pin "3V3") (pinfunction "3V3_3V3") (pintype "bidirectional"))
    )
    (net (code "110") (name "unconnected-(U$1-Pad3V3_2)") (class "Default")
      (node (ref "U$1") (pin "3V3_2") (pinfunction "3V3_2_3V3_2") (pintype "bidirectional"))
    )
    (net (code "111") (name "unconnected-(U$1-Pad3V3_LO)") (class "Default")
      (node (ref "U$1") (pin "3V3_LO") (pinfunction "3V3_LO_3V3_LO") (pintype "bidirectional"))
    )
    (net (code "112") (name "unconnected-(U$1-Pad3{slash}CANTX)") (class "Default")
      (node (ref "U$1") (pin "3/CANTX") (pinfunction "3/CANTX_3/CANTX") (pintype "bidirectional"))
    )
    (net (code "113") (name "unconnected-(U$1-Pad4{slash}CANRX)") (class "Default")
      (node (ref "U$1") (pin "4/CANRX") (pinfunction "4/CANRX_4/CANRX") (pintype "bidirectional"))
    )
    (net (code "114") (name "unconnected-(U$1-Pad9{slash}CS)") (class "Default")
      (node (ref "U$1") (pin "9/CS") (pinfunction "9/CS_9/CS") (pintype "bidirectional"))
    )
    (net (code "115") (name "unconnected-(U$1-Pad17{slash}A3)") (class "Default")
      (node (ref "U$1") (pin "17/A3") (pinfunction "17/A3_17/A3") (pintype "bidirectional"))
    )
    (net (code "116") (name "unconnected-(U$1-Pad20{slash}A6)") (class "Default")
      (node (ref "U$1") (pin "20/A6") (pinfunction "20/A6_20/A6") (pintype "bidirectional"))
    )
    (net (code "117") (name "unconnected-(U$1-Pad21{slash}A7)") (class "Default")
      (node (ref "U$1") (pin "21/A7") (pinfunction "21/A7_21/A7") (pintype "bidirectional"))
    )
    (net (code "118") (name "unconnected-(U$1-Pad22{slash}A8)") (class "Default")
      (node (ref "U$1") (pin "22/A8") (pinfunction "22/A8_22/A8") (pintype "bidirectional"))
    )
    (net (code "119") (name "unconnected-(U$1-Pad23{slash}A9)") (class "Default")
      (node (ref "U$1") (pin "23/A9") (pinfunction "23/A9_23/A9") (pintype "bidirectional"))
    )
    (net (code "120") (name "unconnected-(U$1-Pad24)") (class "Default")
      (node (ref "U$1") (pin "24") (pinfunction "24_24") (pintype "bidirectional"))
    )
    (net (code "121") (name "unconnected-(U$1-Pad25)") (class "Default")
      (node (ref "U$1") (pin "25") (pinfunction "25_25") (pintype "bidirectional"))
    )
    (net (code "122") (name "unconnected-(U$1-Pad26)") (class "Default")
      (node (ref "U$1") (pin "26") (pinfunction "26_26") (pintype "bidirectional"))
    )
    (net (code "123") (name "unconnected-(U$1-Pad27)") (class "Default")
      (node (ref "U$1") (pin "27") (pinfunction "27_27") (pintype "bidirectional"))
    )
    (net (code "124") (name "unconnected-(U$1-Pad28)") (class "Default")
      (node (ref "U$1") (pin "28") (pinfunction "28_28") (pintype "bidirectional"))
    )
    (net (code "125") (name "unconnected-(U$1-Pad29)") (class "Default")
      (node (ref "U$1") (pin "29") (pinfunction "29_29") (pintype "bidirectional"))
    )
    (net (code "126") (name "unconnected-(U$1-Pad30)") (class "Default")
      (node (ref "U$1") (pin "30") (pinfunction "30_30") (pintype "bidirectional"))
    )
    (net (code "127") (name "unconnected-(U$1-Pad31{slash}A12)") (class "Default")
      (node (ref "U$1") (pin "31/A12") (pinfunction "31/A12_31/A12") (pintype "bidirectional"))
    )
    (net (code "128") (name "unconnected-(U$1-Pad32{slash}A13)") (class "Default")
      (node (ref "U$1") (pin "32/A13") (pinfunction "32/A13_32/A13") (pintype "bidirectional"))
    )
    (net (code "129") (name "unconnected-(U$1-Pad33{slash}A14)") (class "Default")
      (node (ref "U$1") (pin "33/A14") (pinfunction "33/A14_33/A14") (pintype "bidirectional"))
    )
    (net (code "130") (name "unconnected-(U$1-Pad34{slash}A15)") (class "Default")
      (node (ref "U$1") (pin "34/A15") (pinfunction "34/A15_34/A15") (pintype "bidirectional"))
    )
    (net (code "131") (name "unconnected-(U$1-Pad36{slash}A17)") (class "Default")
      (node (ref "U$1") (pin "36/A17") (pinfunction "36/A17_36/A17") (pintype "bidirectional"))
    )
    (net (code "132") (name "unconnected-(U$1-Pad37{slash}A18)") (class "Default")
      (node (ref "U$1") (pin "37/A18") (pinfunction "37/A18_37/A18") (pintype "bidirectional"))
    )
    (net (code "133") (name "unconnected-(U$1-Pad38{slash}A19)") (class "Default")
      (node (ref "U$1") (pin "38/A19") (pinfunction "38/A19_38/A19") (pintype "bidirectional"))
    )
    (net (code "134") (name "unconnected-(U$1-Pad39{slash}A20)") (class "Default")
      (node (ref "U$1") (pin "39/A20") (pinfunction "39/A20_39/A20") (pintype "bidirectional"))
    )
    (net (code "135") (name "unconnected-(U$1-PadA10)") (class "Default")
      (node (ref "U$1") (pin "A10") (pinfunction "A10_A10") (pintype "bidirectional"))
    )
    (net (code "136") (name "unconnected-(U$1-PadA11)") (class "Default")
      (node (ref "U$1") (pin "A11") (pinfunction "A11_A11") (pintype "bidirectional"))
    )
    (net (code "137") (name "unconnected-(U$1-PadA22{slash}DAC1)") (class "Default")
      (node (ref "U$1") (pin "A22/DAC1") (pinfunction "A22/DAC1_A22/DAC1") (pintype "bidirectional"))
    )
    (net (code "138") (name "unconnected-(U$1-PadAGND)") (class "Default")
      (node (ref "U$1") (pin "AGND") (pinfunction "AGND_AGND") (pintype "bidirectional"))
    )
    (net (code "139") (name "unconnected-(U$1-PadAREF)") (class "Default")
      (node (ref "U$1") (pin "AREF") (pinfunction "AREF_AREF") (pintype "bidirectional"))
    )
    (net (code "140") (name "unconnected-(U$1-PadGND)") (class "Default")
      (node (ref "U$1") (pin "GND") (pinfunction "GND_GND") (pintype "bidirectional"))
    )
    (net (code "141") (name "unconnected-(U$1-PadGND2)") (class "Default")
      (node (ref "U$1") (pin "GND2") (pinfunction "GND2_GND2") (pintype "bidirectional"))
    )
    (net (code "142") (name "unconnected-(U$1-PadGND3)") (class "Default")
      (node (ref "U$1") (pin "GND3") (pinfunction "GND3_GND3") (pintype "bidirectional"))
    )
    (net (code "143") (name "unconnected-(U$1-PadPROG)") (class "Default")
      (node (ref "U$1") (pin "PROG") (pinfunction "PROG_PROG") (pintype "bidirectional"))
    )
    (net (code "144") (name "unconnected-(U$1-PadRESET)") (class "Default")
      (node (ref "U$1") (pin "RESET") (pinfunction "RESET_RESET") (pintype "bidirectional"))
    )
    (net (code "145") (name "unconnected-(U$1-PadU5V)") (class "Default")
      (node (ref "U$1") (pin "U5V") (pinfunction "U5V_U5V") (pintype "bidirectional"))
    )
    (net (code "146") (name "unconnected-(U$1-PadUD+)") (class "Default")
      (node (ref "U$1") (pin "UD+") (pinfunction "UD+_UD+") (pintype "bidirectional"))
    )
    (net (code "147") (name "unconnected-(U$1-PadUD-)") (class "Default")
      (node (ref "U$1") (pin "UD-") (pinfunction "UD-_UD-") (pintype "bidirectional"))
    )
    (net (code "148") (name "unconnected-(U$1-PadUGND1)") (class "Default")
      (node (ref "U$1") (pin "UGND1") (pinfunction "UGND1_UGND1") (pintype "bidirectional"))
    )
    (net (code "149") (name "unconnected-(U$1-PadUGND2)") (class "Default")
      (node (ref "U$1") (pin "UGND2") (pinfunction "UGND2_UGND2") (pintype "bidirectional"))
    )
    (net (code "150") (name "unconnected-(U$1-PadVBAT)") (class "Default")
      (node (ref "U$1") (pin "VBAT") (pinfunction "VBAT_VBAT") (pintype "bidirectional"))
    )
    (net (code "151") (name "unconnected-(U$1-PadVUSB)") (class "Default")
      (node (ref "U$1") (pin "VUSB") (pinfunction "VUSB_VUSB") (pintype "bidirectional"))
    )
    (net (code "152") (name "unconnected-(U1-NC-Pad8)") (class "Default")
      (node (ref "U1") (pin "8") (pinfunction "NC_8") (pintype "no_connect"))
    )
    (net (code "153") (name "unconnected-(U1-NC-Pad9)") (class "Default")
      (node (ref "U1") (pin "9") (pinfunction "NC_9") (pintype "no_connect"))
    )
    (net (code "154") (name "unconnected-(U1-NC-Pad10)") (class "Default")
      (node (ref "U1") (pin "10") (pinfunction "NC_10") (pintype "no_connect"))
    )
    (net (code "155") (name "unconnected-(U1-NC-Pad11)") (class "Default")
      (node (ref "U1") (pin "11") (pinfunction "NC_11") (pintype "no_connect"))
    )
    (net (code "156") (name "unconnected-(U1-NC-Pad12)") (class "Default")
      (node (ref "U1") (pin "12") (pinfunction "NC_12") (pintype "no_connect"))
    )
    (net (code "157") (name "unconnected-(U1-NC-Pad13)") (class "Default")
      (node (ref "U1") (pin "13") (pinfunction "NC_13") (pintype "no_connect"))
    )
    (net (code "158") (name "unconnected-(U1-SELFTEST-Pad2)") (class "Default")
      (node (ref "U1") (pin "2") (pinfunction "SELFTEST_2") (pintype "bidirectional"))
    )
    (net (code "159") (name "unconnected-(U2-P4-Pad4)") (class "Default")
      (node (ref "U2") (pin "4") (pinfunction "P4_4") (pintype "bidirectional"))
    )
    (net (code "160") (name "unconnected-(U3-P4-Pad4)") (class "Default")
      (node (ref "U3") (pin "4") (pinfunction "P4_4") (pintype "bidirectional"))
    )
    (net (code "161") (name "unconnected-(U7-P4-Pad4)") (class "Default")
      (node (ref "U7") (pin "4") (pinfunction "P4_4") (pintype "bidirectional"))
    )
    (net (code "162") (name "unconnected-(X2-CARD_DETECT1-PadCD2)") (class "Default")
      (node (ref "X2") (pin "CD2") (pinfunction "CARD_DETECT1_CD2") (pintype "passive"))
    )
    (net (code "163") (name "unconnected-(X2-DAT1-Pad8)") (class "Default")
      (node (ref "X2") (pin "8") (pinfunction "DAT1_8") (pintype "bidirectional"))
    )
    (net (code "164") (name "unconnected-(X2-DAT2-Pad1)") (class "Default")
      (node (ref "X2") (pin "1") (pinfunction "DAT2_1") (pintype "bidirectional"))
    )
  )
)
